# tyraka.net
KiCad netlist of a schematic drawn in EAGLE
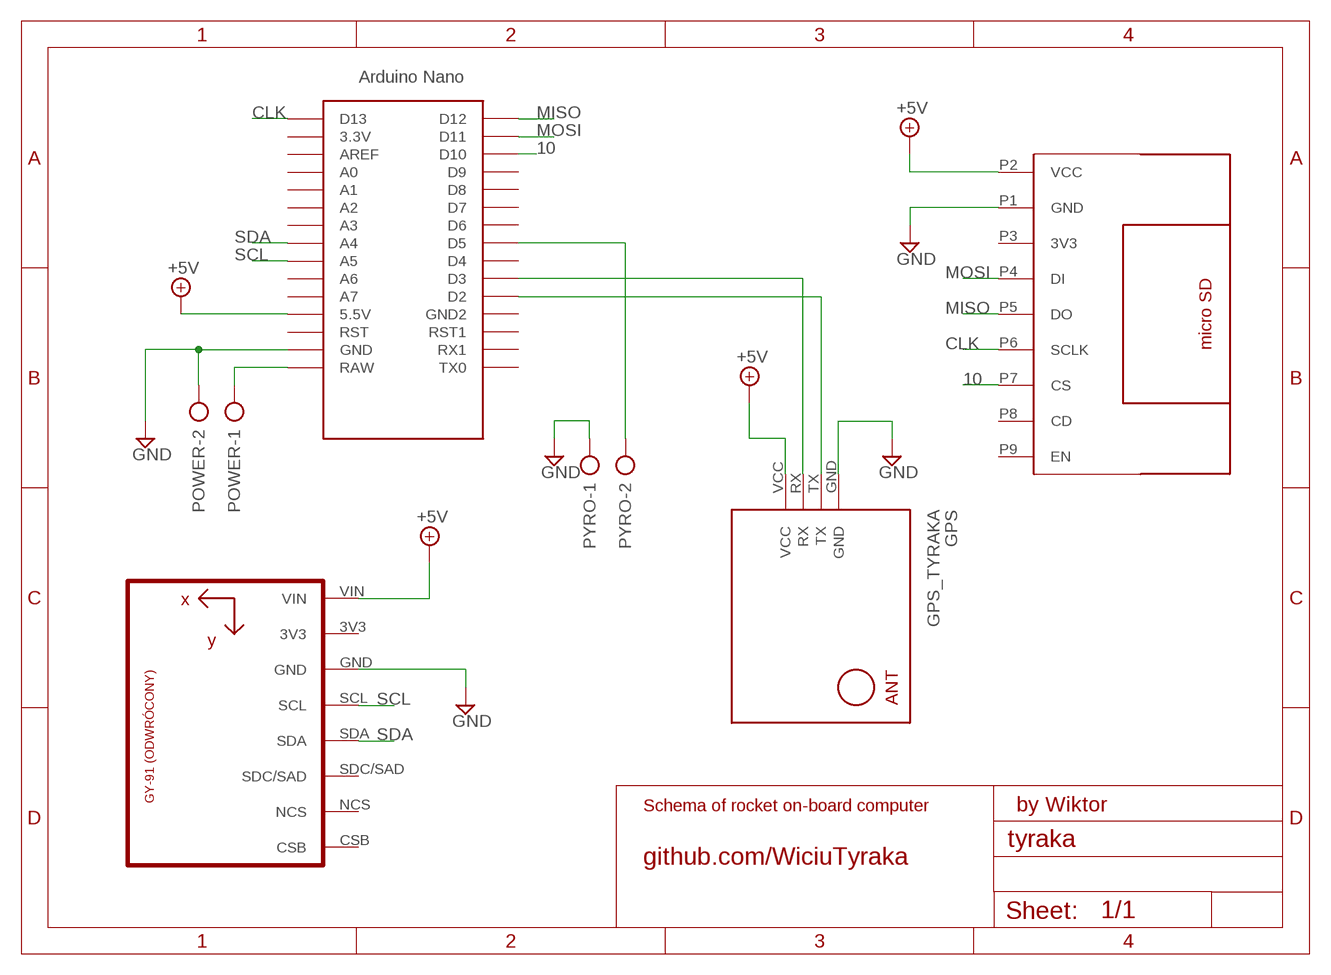
[diagram p0: schematic, sheet 1]

(export (version "E")
  (design (tool "Eeschema 10.0.6"))
  (components
    (comp (ref "ARDUINO")
      (value "NANO")
      (footprint "eagle-import:NANO")
      (libsource (lib "eagle-import") (part "NANO"))
    )
    (comp (ref "GPS")
      (value "GPS_TYRAKA")
      (footprint "eagle-import:GPS-RECEIVER-NEO6M")
      (libsource (lib "eagle-import") (part "GPS_TYRAKA"))
    )
    (comp (ref "POWER")
      (value "AK500/2")
      (footprint "eagle-import:AK500_2")
      (libsource (lib "eagle-import") (part "AK500/2"))
    )
    (comp (ref "PYRO")
      (value "AK500/2")
      (footprint "eagle-import:AK500_2")
      (libsource (lib "eagle-import") (part "AK500/2"))
    )
    (comp (ref "SD1")
      (value "MICRO_SD")
      (footprint "eagle-import:MICRO_SD")
      (libsource (lib "eagle-import") (part "MICRO_SD"))
    )
    (comp (ref "U1")
      (value "GY-521MPU6050")
      (footprint "eagle-import:GY-521")
      (libsource (lib "eagle-import") (part "GY-521MPU6050"))
    )
  )
  (nets
    (net (code "1") (name "+5V") (class "Default")
      (node (ref "ARDUINO") (pin "5V") (pinfunction "5.5V_5V") (pintype "bidirectional"))
      (node (ref "GPS") (pin "VCC") (pinfunction "VCC_VCC") (pintype "power_in"))
      (node (ref "SD1") (pin "P2") (pinfunction "VCC_P2") (pintype "power_in"))
      (node (ref "U1") (pin "VIN") (pinfunction "VIN_VIN") (pintype "bidirectional"))
    )
    (net (code "2") (name "/10") (class "Default")
      (node (ref "ARDUINO") (pin "D10") (pinfunction "D10_D10") (pintype "bidirectional"))
      (node (ref "SD1") (pin "P7") (pinfunction "CS_P7") (pintype "bidirectional"))
    )
    (net (code "3") (name "/CLK") (class "Default")
      (node (ref "ARDUINO") (pin "D13") (pinfunction "D13_D13") (pintype "bidirectional"))
      (node (ref "SD1") (pin "P6") (pinfunction "SCLK_P6") (pintype "bidirectional"))
    )
    (net (code "4") (name "/MISO") (class "Default")
      (node (ref "ARDUINO") (pin "D12") (pinfunction "D12_D12") (pintype "bidirectional"))
      (node (ref "SD1") (pin "P5") (pinfunction "DO_P5") (pintype "bidirectional"))
    )
    (net (code "5") (name "/MOSI") (class "Default")
      (node (ref "ARDUINO") (pin "D11") (pinfunction "D11_D11") (pintype "bidirectional"))
      (node (ref "SD1") (pin "P4") (pinfunction "DI_P4") (pintype "bidirectional"))
    )
    (net (code "6") (name "/SCL") (class "Default")
      (node (ref "ARDUINO") (pin "A5") (pinfunction "A5_A5") (pintype "bidirectional"))
      (node (ref "U1") (pin "SCL") (pinfunction "SCL_SCL") (pintype "bidirectional"))
    )
    (net (code "7") (name "/SDA") (class "Default")
      (node (ref "ARDUINO") (pin "A4") (pinfunction "A4_A4") (pintype "bidirectional"))
      (node (ref "U1") (pin "SDA") (pinfunction "SDA_SDA") (pintype "bidirectional"))
    )
    (net (code "8") (name "GND") (class "Default")
      (node (ref "ARDUINO") (pin "GND") (pinfunction "GND_GND") (pintype "bidirectional"))
      (node (ref "GPS") (pin "GND") (pinfunction "GND_GND") (pintype "power_in"))
      (node (ref "POWER") (pin "2") (pinfunction "KL_2") (pintype "passive"))
      (node (ref "PYRO") (pin "1") (pinfunction "KL_1") (pintype "passive"))
      (node (ref "SD1") (pin "P1") (pinfunction "GND_P1") (pintype "power_in"))
      (node (ref "U1") (pin "GND") (pinfunction "GND_GND") (pintype "bidirectional"))
    )
    (net (code "9") (name "Net-(ARDUINO-PadD2)") (class "Default")
      (node (ref "ARDUINO") (pin "D2") (pinfunction "D2_D2") (pintype "bidirectional"))
      (node (ref "GPS") (pin "TX") (pinfunction "TX_TX") (pintype "bidirectional"))
    )
    (net (code "10") (name "Net-(ARDUINO-PadD3)") (class "Default")
      (node (ref "ARDUINO") (pin "D3") (pinfunction "D3_D3") (pintype "bidirectional"))
      (node (ref "GPS") (pin "RX") (pinfunction "RX_RX") (pintype "bidirectional"))
    )
    (net (code "11") (name "Net-(POWERA-KL)") (class "Default")
      (node (ref "ARDUINO") (pin "RAW") (pinfunction "RAW_RAW") (pintype "bidirectional"))
      (node (ref "POWER") (pin "1") (pinfunction "KL_1") (pintype "passive"))
    )
    (net (code "12") (name "Net-(PYROB-KL)") (class "Default")
      (node (ref "ARDUINO") (pin "D5") (pinfunction "D5_D5") (pintype "bidirectional"))
      (node (ref "PYRO") (pin "2") (pinfunction "KL_2") (pintype "passive"))
    )
    (net (code "13") (name "unconnected-(ARDUINO-GND2-PadGND1)") (class "Default")
      (node (ref "ARDUINO") (pin "GND1") (pinfunction "GND2_GND1") (pintype "bidirectional"))
    )
    (net (code "14") (name "unconnected-(ARDUINO-Pad3.3V)") (class "Default")
      (node (ref "ARDUINO") (pin "3.3V") (pinfunction "3.3V_3.3V") (pintype "bidirectional"))
    )
    (net (code "15") (name "unconnected-(ARDUINO-PadA0)") (class "Default")
      (node (ref "ARDUINO") (pin "A0") (pinfunction "A0_A0") (pintype "bidirectional"))
    )
    (net (code "16") (name "unconnected-(ARDUINO-PadA1)") (class "Default")
      (node (ref "ARDUINO") (pin "A1") (pinfunction "A1_A1") (pintype "bidirectional"))
    )
    (net (code "17") (name "unconnected-(ARDUINO-PadA2)") (class "Default")
      (node (ref "ARDUINO") (pin "A2") (pinfunction "A2_A2") (pintype "bidirectional"))
    )
    (net (code "18") (name "unconnected-(ARDUINO-PadA3)") (class "Default")
      (node (ref "ARDUINO") (pin "A3") (pinfunction "A3_A3") (pintype "bidirectional"))
    )
    (net (code "19") (name "unconnected-(ARDUINO-PadA6)") (class "Default")
      (node (ref "ARDUINO") (pin "A6") (pinfunction "A6_A6") (pintype "bidirectional"))
    )
    (net (code "20") (name "unconnected-(ARDUINO-PadA7)") (class "Default")
      (node (ref "ARDUINO") (pin "A7") (pinfunction "A7_A7") (pintype "bidirectional"))
    )
    (net (code "21") (name "unconnected-(ARDUINO-PadAREF)") (class "Default")
      (node (ref "ARDUINO") (pin "AREF") (pinfunction "AREF_AREF") (pintype "bidirectional"))
    )
    (net (code "22") (name "unconnected-(ARDUINO-PadD4)") (class "Default")
      (node (ref "ARDUINO") (pin "D4") (pinfunction "D4_D4") (pintype "bidirectional"))
    )
    (net (code "23") (name "unconnected-(ARDUINO-PadD6)") (class "Default")
      (node (ref "ARDUINO") (pin "D6") (pinfunction "D6_D6") (pintype "bidirectional"))
    )
    (net (code "24") (name "unconnected-(ARDUINO-PadD7)") (class "Default")
      (node (ref "ARDUINO") (pin "D7") (pinfunction "D7_D7") (pintype "bidirectional"))
    )
    (net (code "25") (name "unconnected-(ARDUINO-PadD8)") (class "Default")
      (node (ref "ARDUINO") (pin "D8") (pinfunction "D8_D8") (pintype "bidirectional"))
    )
    (net (code "26") (name "unconnected-(ARDUINO-PadD9)") (class "Default")
      (node (ref "ARDUINO") (pin "D9") (pinfunction "D9_D9") (pintype "bidirectional"))
    )
    (net (code "27") (name "unconnected-(ARDUINO-PadICSP1)") (class "Default")
      (node (ref "ARDUINO") (pin "ICSP1") (pinfunction "ICSP1_ICSP1") (pintype "bidirectional"))
    )
    (net (code "28") (name "unconnected-(ARDUINO-PadICSP2)") (class "Default")
      (node (ref "ARDUINO") (pin "ICSP2") (pinfunction "ICSP2_ICSP2") (pintype "bidirectional"))
    )
    (net (code "29") (name "unconnected-(ARDUINO-PadICSP3)") (class "Default")
      (node (ref "ARDUINO") (pin "ICSP3") (pinfunction "ICSP3_ICSP3") (pintype "bidirectional"))
    )
    (net (code "30") (name "unconnected-(ARDUINO-PadICSP4)") (class "Default")
      (node (ref "ARDUINO") (pin "ICSP4") (pinfunction "ICSP4_ICSP4") (pintype "bidirectional"))
    )
    (net (code "31") (name "unconnected-(ARDUINO-PadICSP5)") (class "Default")
      (node (ref "ARDUINO") (pin "ICSP5") (pinfunction "ICSP5_ICSP5") (pintype "bidirectional"))
    )
    (net (code "32") (name "unconnected-(ARDUINO-PadICSP6)") (class "Default")
      (node (ref "ARDUINO") (pin "ICSP6") (pinfunction "ICSP6_ICSP6") (pintype "bidirectional"))
    )
    (net (code "33") (name "unconnected-(ARDUINO-PadRST)") (class "Default")
      (node (ref "ARDUINO") (pin "RST") (pinfunction "RST_RST") (pintype "bidirectional"))
    )
    (net (code "34") (name "unconnected-(ARDUINO-PadRST1)") (class "Default")
      (node (ref "ARDUINO") (pin "RST1") (pinfunction "RST1_RST1") (pintype "bidirectional"))
    )
    (net (code "35") (name "unconnected-(ARDUINO-PadRX1)") (class "Default")
      (node (ref "ARDUINO") (pin "RX1") (pinfunction "RX1_RX1") (pintype "bidirectional"))
    )
    (net (code "36") (name "unconnected-(ARDUINO-PadTX0)") (class "Default")
      (node (ref "ARDUINO") (pin "TX0") (pinfunction "TX0_TX0") (pintype "bidirectional"))
    )
    (net (code "37") (name "unconnected-(SD1-3V3-PadP3)") (class "Default")
      (node (ref "SD1") (pin "P3") (pinfunction "3V3_P3") (pintype "bidirectional"))
    )
    (net (code "38") (name "unconnected-(SD1-CD-PadP8)") (class "Default")
      (node (ref "SD1") (pin "P8") (pinfunction "CD_P8") (pintype "bidirectional"))
    )
    (net (code "39") (name "unconnected-(SD1-EN-PadP9)") (class "Default")
      (node (ref "SD1") (pin "P9") (pinfunction "EN_P9") (pintype "bidirectional"))
    )
    (net (code "40") (name "unconnected-(U1-Pad3V3)") (class "Default")
      (node (ref "U1") (pin "3V3") (pinfunction "3V3_3V3") (pintype "bidirectional"))
    )
    (net (code "41") (name "unconnected-(U1-PadCSB)") (class "Default")
      (node (ref "U1") (pin "CSB") (pinfunction "CSB_CSB") (pintype "bidirectional"))
    )
    (net (code "42") (name "unconnected-(U1-PadNCS)") (class "Default")
      (node (ref "U1") (pin "NCS") (pinfunction "NCS_NCS") (pintype "bidirectional"))
    )
    (net (code "43") (name "unconnected-(U1-PadSDC{slash}SAD)") (class "Default")
      (node (ref "U1") (pin "SDC/SAD") (pinfunction "SDC/SAD_SDC/SAD") (pintype "bidirectional"))
    )
  )
)
